# Face_MainBack1V0.net
KiCad netlist of a schematic drawn in Altium Designer
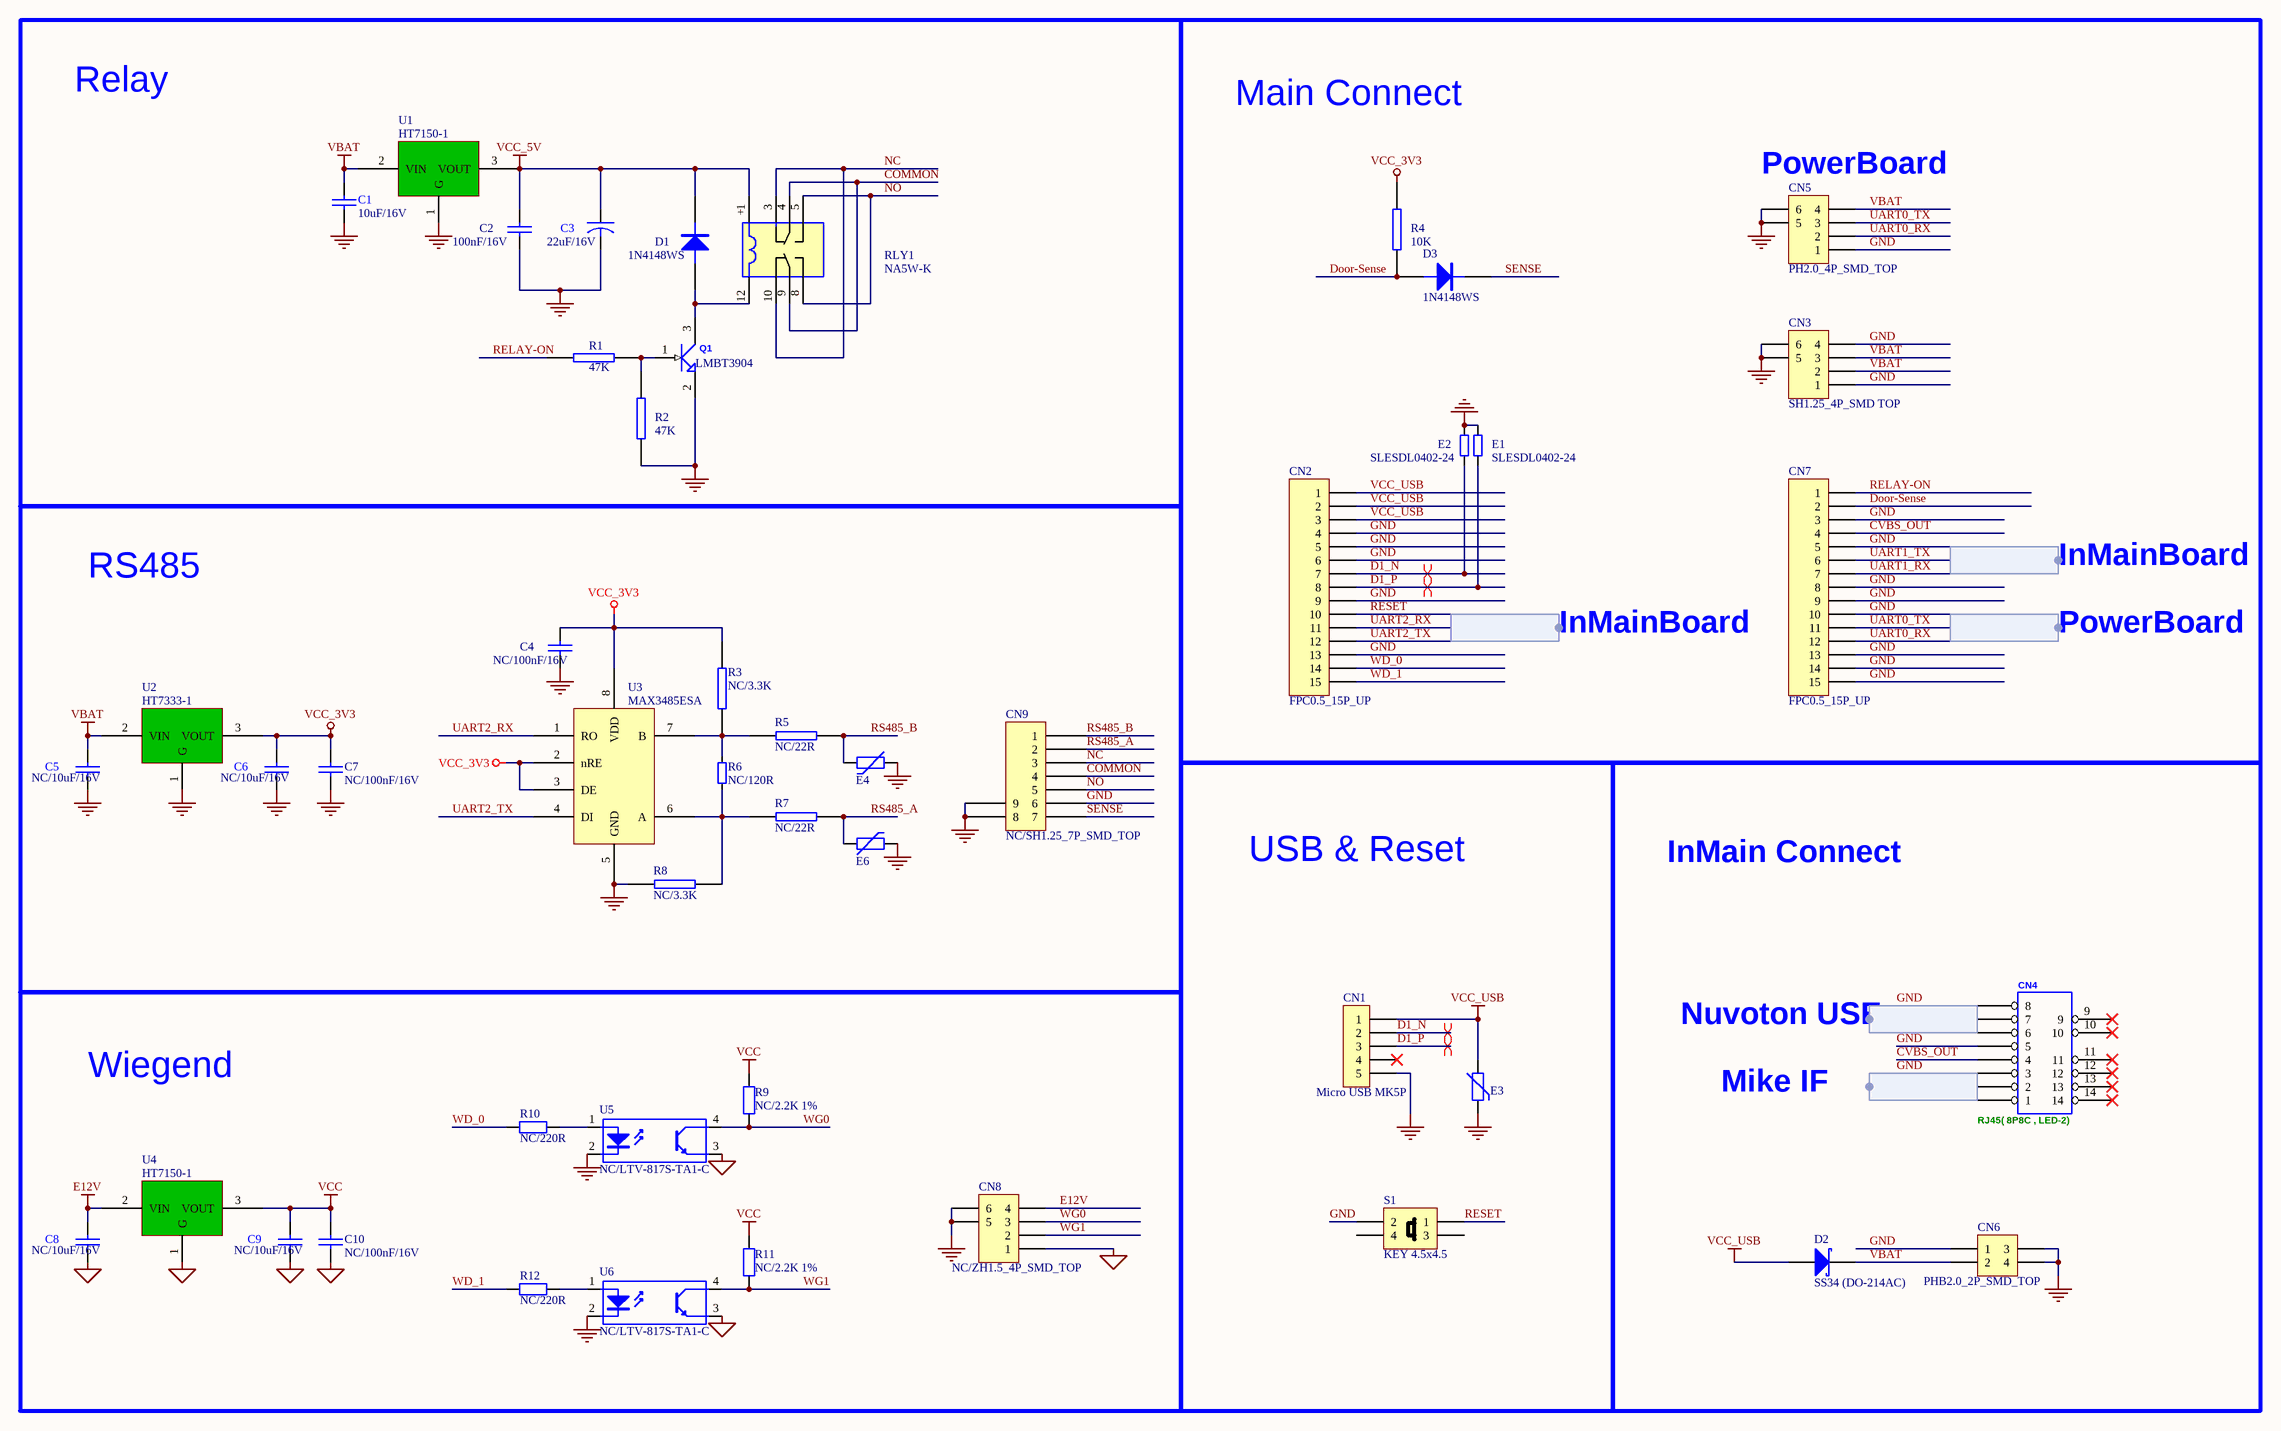
[diagram p0: Face_MainBack1V0.SchDoc]

(export (version "E")
  (design (tool "Eeschema 10.0.6"))
  (components
    (comp (ref "C1")
      (value "10uF/16V")
      (footprint "C0805")
      (description "10uF/16V 10% 0805 X7R ROHS")
      (libsource (lib "*") (part "CAP"))
    )
    (comp (ref "C2")
      (value "100nF/16V")
      (footprint "C0402")
      (description "100nF/16V 10% 0402 X7R ROHS")
      (libsource (lib "*") (part "CAP"))
    )
    (comp (ref "C3")
      (value "22uF/16V")
      (footprint "C0805")
      (description "22uF/16V 20% 0805 X7R ROHS")
      (libsource (lib "*") (part "CAPACITOR"))
    )
    (comp (ref "C4")
      (value "NC/100nF/16V")
      (footprint "C0402")
      (description "100nF/16V 10% 0402 X7R ROHS")
      (libsource (lib "*") (part "CAP"))
    )
    (comp (ref "C5")
      (value "NC/10uF/16V")
      (footprint "C0805")
      (description "10uF/16V 10% 0805 X7R ROHS")
      (libsource (lib "*") (part "CAP"))
    )
    (comp (ref "C6")
      (value "NC/10uF/16V")
      (footprint "C0805")
      (description "10uF/16V 10% 0805 X7R ROHS")
      (libsource (lib "*") (part "CAP"))
    )
    (comp (ref "C7")
      (value "NC/100nF/16V")
      (footprint "C0402")
      (description "100nF/16V 10% 0402 X7R ROHS")
      (libsource (lib "*") (part "CAP"))
    )
    (comp (ref "C8")
      (value "NC/10uF/16V")
      (footprint "C0805")
      (description "10uF/16V 10% 0805 X7R ROHS")
      (libsource (lib "*") (part "CAP"))
    )
    (comp (ref "C9")
      (value "NC/10uF/16V")
      (footprint "C0805")
      (description "10uF/16V 10% 0805 X7R ROHS")
      (libsource (lib "*") (part "CAP"))
    )
    (comp (ref "C10")
      (value "NC/100nF/16V")
      (footprint "C0402")
      (description "100nF/16V 10% 0402 X7R ROHS")
      (libsource (lib "*") (part "CAP"))
    )
    (comp (ref "CN1")
      (value "micro USB")
      (footprint "MICRO_5P_??")
      (description "Micro USB")
      (fields (field (name "ALTIUM_UNNAMED_1") "Micro USB MK5P"))
      (libsource (lib "PCB_Project") (part "CON5"))
    )
    (comp (ref "CN2")
      (value "FPC0.5_15P_UP")
      (footprint "FPC15_0.5_BOTTOM_Drawer")
      (fields (field (name "PUBLISHER") "Altium Limited"))
      (libsource (lib "Miscellaneous Connectors") (part "Header 15"))
    )
    (comp (ref "CN3")
      (value "SH1.25_4P_SMD TOP")
      (footprint "SH1.25_4P_SMD_TOP")
      (fields (field (name "PUBLISHER") "Altium Limited"))
      (libsource (lib "S10_Project") (part "Header 4"))
    )
    (comp (ref "CN4") (value "RJ45( 8P8C , LED-2)") (footprint "RJ45_S") (libsource (lib "*") (part "RJ45")))
    (comp (ref "CN5")
      (value "PH2.0_4P_SMD_TOP")
      (footprint "PH2.0_4P_SMD_TOP")
      (fields (field (name "PUBLISHER") "Altium Limited"))
      (libsource (lib "S10_Project") (part "Header 4"))
    )
    (comp (ref "CN6")
      (value "PHB2.0_2P_SMD_TOP")
      (footprint "PH2.0_2P_SMD_TOP")
      (libsource (lib "FIX Board1V1") (part "Header 2"))
    )
    (comp (ref "CN7")
      (value "FPC0.5_15P_UP")
      (footprint "FPC15_0.5_BOTTOM_Drawer")
      (fields (field (name "PUBLISHER") "Altium Limited"))
      (libsource (lib "Miscellaneous Connectors") (part "Header 15"))
    )
    (comp (ref "CN8")
      (value "NC/ZH1.5_4P_SMD_TOP")
      (footprint "ZH1.5_4P_SMD_TOP")
      (description "ZH1.5_4P_SMD_TOP")
      (fields (field (name "PUBLISHER") "Altium Limited"))
      (libsource (lib "S10_Project") (part "Header 4"))
    )
    (comp (ref "CN9")
      (value "NC/SH1.25_7P_SMD_TOP")
      (footprint "SH1.25_7P_SMD_TOP")
      (description "SH1.25_7P_SMD_TOP")
      (libsource (lib "Schlib1") (part "Component_1"))
    )
    (comp (ref "D1") (value "1N4148WS") (footprint "SOD-323") (libsource (lib "*") (part "DIODE")))
    (comp (ref "D2")
      (value "SS34 (DO-214AC)")
      (footprint "DO-214AC")
      (libsource (lib "LM") (part "SS34 (DO-214AC)"))
    )
    (comp (ref "D3") (value "1N4148WS") (footprint "SOD-323") (libsource (lib "*") (part "DIODE")))
    (comp (ref "E1")
      (value "SLESDL0402-24")
      (footprint "L0402")
      (description "SLESDL0402-24 0402 ROHS")
      (libsource (lib "LM") (part "RES"))
    )
    (comp (ref "E2")
      (value "SLESDL0402-24")
      (footprint "L0402")
      (description "SLESDL0402-24 0402 ROHS")
      (libsource (lib "LM") (part "RES"))
    )
    (comp (ref "E3")
      (value "SFI0402-050E330NP-LF")
      (footprint "R0402")
      (libsource (lib "ZhuhaiSch") (part "VARISTOR"))
    )
    (comp (ref "E4")
      (value "NC/SFI0402-050E330NP-LF")
      (footprint "R0402")
      (description "SFI0402-050E330NP-LF")
      (libsource (lib "ZhuhaiSch") (part "VARISTOR"))
    )
    (comp (ref "E6")
      (value "NC/SFI0402-050E330NP-LF")
      (footprint "R0402")
      (description "SFI0402-050E330NP-LF")
      (libsource (lib "ZhuhaiSch") (part "VARISTOR"))
    )
    (comp (ref "Q1")
      (value "LMBT3904 (SOT-23-3)")
      (footprint "SOT-23-3")
      (fields (field (name "ALTIUM_UNNAMED_1") "LMBT3904"))
      (libsource (lib "*") (part "NPN1"))
    )
    (comp (ref "R1")
      (value "47K")
      (footprint "R0402")
      (description "47K +/-5% 1/16W 0402 ROHS")
      (libsource (lib "*") (part "RES2"))
    )
    (comp (ref "R2")
      (value "47K")
      (footprint "R0402")
      (description "47K +/-5% 1/16W 0402 ROHS")
      (libsource (lib "*") (part "RES2"))
    )
    (comp (ref "R3")
      (value "NC/3.3K")
      (footprint "R0402")
      (description "3.3K +/-5% 1/16W 0402 ROHS")
      (libsource (lib "*") (part "RES2"))
    )
    (comp (ref "R4")
      (value "10K")
      (footprint "R0402")
      (description "10K +/-5% 1/16W 0402 ROHS")
      (libsource (lib "*") (part "RES2"))
    )
    (comp (ref "R5")
      (value "NC/22R")
      (footprint "R0402")
      (description "22R +/-5% 1/16W 0402 ROHS")
      (libsource (lib "*") (part "RES2"))
    )
    (comp (ref "R6")
      (value "NC/120R")
      (footprint "R0402")
      (description "120R +/-5% 1/16W 0402 ROHS")
      (libsource (lib "FL01M1V5") (part "RES2"))
    )
    (comp (ref "R7")
      (value "NC/22R")
      (footprint "R0402")
      (description "22R +/-5% 1/16W 0402 ROHS")
      (libsource (lib "*") (part "RES2"))
    )
    (comp (ref "R8")
      (value "NC/3.3K")
      (footprint "R0402")
      (description "3.3K +/-5% 1/16W 0402 ROHS")
      (libsource (lib "*") (part "RES2"))
    )
    (comp (ref "R9")
      (value "NC/2.2K 1%")
      (footprint "R0402")
      (description "2.2K +/-1% 1/16W 0402 ROHS")
      (fields (field (name "PUBLISHER") "Altium Limited"))
      (libsource (lib "Miscellaneous Devices") (part "Res2"))
    )
    (comp (ref "R10")
      (value "NC/220R")
      (footprint "R0402")
      (description "220R +/-5% 1/16W 0402 ROHS")
      (fields (field (name "PUBLISHER") "Altium Limited"))
      (libsource (lib "") (part "Res2_1"))
    )
    (comp (ref "R11")
      (value "NC/2.2K 1%")
      (footprint "R0402")
      (description "2.2K +/-1% 1/16W 0402 ROHS")
      (fields (field (name "PUBLISHER") "Altium Limited"))
      (libsource (lib "Miscellaneous Devices") (part "Res2"))
    )
    (comp (ref "R12")
      (value "NC/220R")
      (footprint "R0402")
      (description "220R +/-5% 1/16W 0402 ROHS")
      (fields (field (name "PUBLISHER") "Altium Limited"))
      (libsource (lib "") (part "Res2_1"))
    )
    (comp (ref "RLY1")
      (value "FUJITSU NA5W-K     DPDT-BM 5V")
      (footprint "NA12W-K")
      (fields (field (name "ALTIUM_UNNAMED_1") "NA5W-K"))
      (libsource (lib "*") (part "RELAY4"))
    )
    (comp (ref "S1")
      (value "KEY 4.5x4.5")
      (footprint "KEY4.5*4.5-5mm-R")
      (description "KEY6x6x14")
      (fields (field (name "PUBLISHER") "Altium Limited"))
      (libsource (lib "*") (part "Header 2X2H"))
    )
    (comp (ref "U1")
      (value "HT7150-1 (SOT-89)")
      (footprint "SOT-89")
      (description "IC")
      (fields (field (name "ALTIUM_UNNAMED_1") "HT7150-1"))
      (libsource (lib "*") (part "HT7333"))
    )
    (comp (ref "U2")
      (value "NC/HT7333-1 (SOT-89)")
      (footprint "SOT-89")
      (fields (field (name "ALTIUM_UNNAMED_1") "HT7333-1"))
      (libsource (lib "*") (part "HT7333"))
    )
    (comp (ref "U3")
      (value "NC/MAX3485ESA(SOIC-8)")
      (footprint "SOIC8")
      (fields (field (name "ALTIUM_UNNAMED_1") "MAX3485ESA"))
      (libsource (lib "*") (part "MAX485"))
    )
    (comp (ref "U4")
      (value "NC/HT7150-1 (SOT-89)")
      (footprint "SOT-89")
      (fields (field (name "ALTIUM_UNNAMED_1") "HT7150-1"))
      (libsource (lib "*") (part "HT7333"))
    )
    (comp (ref "U5")
      (value "NC/LTV-817S-TA1-C")
      (footprint "LTV-817S-TA1-C")
      (description "LTV-817S-TA1-C")
      (fields (field (name "PUBLISHER") "Altium Limited"))
      (libsource (lib "Miscellaneous Devices") (part "Optoisolator1"))
    )
    (comp (ref "U6")
      (value "NC/LTV-817S-TA1-C")
      (footprint "LTV-817S-TA1-C")
      (description "LTV-817S-TA1-C")
      (fields (field (name "PUBLISHER") "Altium Limited"))
      (libsource (lib "Miscellaneous Devices") (part "Optoisolator1"))
    )
  )
  (nets
    (net (code "1") (name "/COMMON") (class "Default")
      (node (ref "CN9") (pin "4") (pinfunction "4_4") (pintype "passive"))
      (node (ref "RLY1") (pin "4") (pinfunction "4_4") (pintype "passive"))
      (node (ref "RLY1") (pin "9") (pinfunction "9_9") (pintype "passive"))
    )
    (net (code "2") (name "/CVBS_OUT") (class "Default")
      (node (ref "CN4") (pin "4") (pinfunction "4_4") (pintype "passive"))
      (node (ref "CN7") (pin "4") (pinfunction "4_4") (pintype "passive"))
    )
    (net (code "3") (name "/D1_N") (class "Default")
      (node (ref "CN1") (pin "2") (pinfunction "2_2") (pintype "passive"))
      (node (ref "CN2") (pin "7") (pinfunction "7_7") (pintype "passive"))
      (node (ref "E2") (pin "2") (pinfunction "2_2") (pintype "passive"))
    )
    (net (code "4") (name "/D1_P") (class "Default")
      (node (ref "CN1") (pin "3") (pinfunction "3_3") (pintype "passive"))
      (node (ref "CN2") (pin "8") (pinfunction "8_8") (pintype "passive"))
      (node (ref "E1") (pin "1") (pinfunction "1_1") (pintype "passive"))
    )
    (net (code "5") (name "/Door-Sense") (class "Default")
      (node (ref "CN7") (pin "2") (pinfunction "2_2") (pintype "passive"))
      (node (ref "D3") (pin "1") (pinfunction "A_1") (pintype "passive"))
      (node (ref "R4") (pin "2") (pinfunction "2_2") (pintype "passive"))
    )
    (net (code "6") (name "/NC") (class "Default")
      (node (ref "CN9") (pin "3") (pinfunction "3_3") (pintype "passive"))
      (node (ref "RLY1") (pin "10") (pinfunction "10_10") (pintype "passive"))
      (node (ref "RLY1") (pin "3") (pinfunction "3_3") (pintype "passive"))
    )
    (net (code "7") (name "/NO") (class "Default")
      (node (ref "CN9") (pin "5") (pinfunction "5_5") (pintype "passive"))
      (node (ref "RLY1") (pin "5") (pinfunction "5_5") (pintype "passive"))
      (node (ref "RLY1") (pin "8") (pinfunction "8_8") (pintype "passive"))
    )
    (net (code "8") (name "/RELAY-ON") (class "Default")
      (node (ref "CN7") (pin "1") (pinfunction "1_1") (pintype "passive"))
      (node (ref "R1") (pin "2") (pinfunction "2_2") (pintype "passive"))
    )
    (net (code "9") (name "/RESET") (class "Default")
      (node (ref "CN2") (pin "10") (pinfunction "10_10") (pintype "passive"))
      (node (ref "S1") (pin "1") (pinfunction "1_1") (pintype "passive"))
    )
    (net (code "10") (name "/RS485_A") (class "Default")
      (node (ref "CN9") (pin "2") (pinfunction "2_2") (pintype "passive"))
      (node (ref "E6") (pin "1") (pinfunction "1_1") (pintype "passive"))
      (node (ref "R7") (pin "2") (pinfunction "2_2") (pintype "passive"))
    )
    (net (code "11") (name "/RS485_B") (class "Default")
      (node (ref "CN9") (pin "1") (pinfunction "1_1") (pintype "passive"))
      (node (ref "E4") (pin "2") (pinfunction "2_2") (pintype "passive"))
      (node (ref "R5") (pin "2") (pinfunction "2_2") (pintype "passive"))
    )
    (net (code "12") (name "/SENSE") (class "Default")
      (node (ref "CN9") (pin "7") (pinfunction "7_7") (pintype "passive"))
      (node (ref "D3") (pin "2") (pinfunction "K_2") (pintype "passive"))
    )
    (net (code "13") (name "/UART0_RX") (class "Default")
      (node (ref "CN5") (pin "2") (pinfunction "2_2") (pintype "passive"))
      (node (ref "CN7") (pin "12") (pinfunction "12_12") (pintype "passive"))
    )
    (net (code "14") (name "/UART0_TX") (class "Default")
      (node (ref "CN5") (pin "3") (pinfunction "3_3") (pintype "passive"))
      (node (ref "CN7") (pin "11") (pinfunction "11_11") (pintype "passive"))
    )
    (net (code "15") (name "/UART1_RX") (class "Default")
      (node (ref "CN4") (pin "1") (pinfunction "1_1") (pintype "passive"))
      (node (ref "CN7") (pin "7") (pinfunction "7_7") (pintype "passive"))
    )
    (net (code "16") (name "/UART1_TX") (class "Default")
      (node (ref "CN4") (pin "2") (pinfunction "2_2") (pintype "passive"))
      (node (ref "CN7") (pin "6") (pinfunction "6_6") (pintype "passive"))
    )
    (net (code "17") (name "/UART2_RX") (class "Default")
      (node (ref "CN2") (pin "11") (pinfunction "11_11") (pintype "passive"))
      (node (ref "CN4") (pin "7") (pinfunction "7_7") (pintype "passive"))
      (node (ref "U3") (pin "1") (pinfunction "RO_1") (pintype "passive"))
    )
    (net (code "18") (name "/UART2_TX") (class "Default")
      (node (ref "CN2") (pin "12") (pinfunction "12_12") (pintype "passive"))
      (node (ref "CN4") (pin "6") (pinfunction "6_6") (pintype "passive"))
      (node (ref "U3") (pin "4") (pinfunction "DI_4") (pintype "passive"))
    )
    (net (code "19") (name "/WD_0") (class "Default")
      (node (ref "CN2") (pin "14") (pinfunction "14_14") (pintype "passive"))
      (node (ref "R10") (pin "1") (pinfunction "1_1") (pintype "passive"))
    )
    (net (code "20") (name "/WD_1") (class "Default")
      (node (ref "CN2") (pin "15") (pinfunction "15_15") (pintype "passive"))
      (node (ref "R12") (pin "1") (pinfunction "1_1") (pintype "passive"))
    )
    (net (code "21") (name "/WG0") (class "Default")
      (node (ref "CN8") (pin "3") (pinfunction "3_3") (pintype "passive"))
      (node (ref "R9") (pin "1") (pinfunction "1_1") (pintype "passive"))
      (node (ref "U5") (pin "4") (pinfunction "C_4") (pintype "passive"))
    )
    (net (code "22") (name "/WG1") (class "Default")
      (node (ref "CN8") (pin "2") (pinfunction "2_2") (pintype "passive"))
      (node (ref "R11") (pin "1") (pinfunction "1_1") (pintype "passive"))
      (node (ref "U6") (pin "4") (pinfunction "C_4") (pintype "passive"))
    )
    (net (code "23") (name "E12V") (class "Default")
      (node (ref "C8") (pin "2") (pinfunction "2_2") (pintype "passive"))
      (node (ref "CN8") (pin "4") (pinfunction "4_4") (pintype "passive"))
      (node (ref "U4") (pin "2") (pinfunction "VIN_2") (pintype "passive"))
    )
    (net (code "24") (name "FGND") (class "Default")
      (node (ref "C10") (pin "1") (pinfunction "1_1") (pintype "passive"))
      (node (ref "C8") (pin "1") (pinfunction "1_1") (pintype "passive"))
      (node (ref "C9") (pin "1") (pinfunction "1_1") (pintype "passive"))
      (node (ref "CN8") (pin "1") (pinfunction "1_1") (pintype "passive"))
      (node (ref "U4") (pin "1") (pinfunction "G_1") (pintype "passive"))
      (node (ref "U5") (pin "3") (pinfunction "E_3") (pintype "passive"))
      (node (ref "U6") (pin "3") (pinfunction "E_3") (pintype "passive"))
    )
    (net (code "25") (name "GND") (class "Default")
      (node (ref "C1") (pin "2") (pinfunction "2_2") (pintype "passive"))
      (node (ref "C2") (pin "1") (pinfunction "1_1") (pintype "passive"))
      (node (ref "C3") (pin "2") (pinfunction "2_2") (pintype "passive"))
      (node (ref "C4") (pin "1") (pinfunction "1_1") (pintype "passive"))
      (node (ref "C5") (pin "1") (pinfunction "1_1") (pintype "passive"))
      (node (ref "C6") (pin "1") (pinfunction "1_1") (pintype "passive"))
      (node (ref "C7") (pin "1") (pinfunction "1_1") (pintype "passive"))
      (node (ref "CN1") (pin "5") (pinfunction "5_5") (pintype "passive"))
      (node (ref "CN2") (pin "13") (pinfunction "13_13") (pintype "passive"))
      (node (ref "CN2") (pin "4") (pinfunction "4_4") (pintype "passive"))
      (node (ref "CN2") (pin "5") (pinfunction "5_5") (pintype "passive"))
      (node (ref "CN2") (pin "6") (pinfunction "6_6") (pintype "passive"))
      (node (ref "CN2") (pin "9") (pinfunction "9_9") (pintype "passive"))
      (node (ref "CN3") (pin "1") (pinfunction "1_1") (pintype "passive"))
      (node (ref "CN3") (pin "4") (pinfunction "4_4") (pintype "passive"))
      (node (ref "CN3") (pin "5") (pinfunction "5_5") (pintype "passive"))
      (node (ref "CN3") (pin "6") (pinfunction "6_6") (pintype "passive"))
      (node (ref "CN4") (pin "3") (pinfunction "3_3") (pintype "passive"))
      (node (ref "CN4") (pin "5") (pinfunction "5_5") (pintype "passive"))
      (node (ref "CN4") (pin "8") (pinfunction "8_8") (pintype "passive"))
      (node (ref "CN5") (pin "1") (pinfunction "1_1") (pintype "passive"))
      (node (ref "CN5") (pin "5") (pinfunction "5_5") (pintype "passive"))
      (node (ref "CN5") (pin "6") (pinfunction "6_6") (pintype "passive"))
      (node (ref "CN6") (pin "1") (pinfunction "1_1") (pintype "passive"))
      (node (ref "CN6") (pin "3") (pinfunction "3_3") (pintype "passive"))
      (node (ref "CN6") (pin "4") (pinfunction "4_4") (pintype "passive"))
      (node (ref "CN7") (pin "10") (pinfunction "10_10") (pintype "passive"))
      (node (ref "CN7") (pin "13") (pinfunction "13_13") (pintype "passive"))
      (node (ref "CN7") (pin "14") (pinfunction "14_14") (pintype "passive"))
      (node (ref "CN7") (pin "15") (pinfunction "15_15") (pintype "passive"))
      (node (ref "CN7") (pin "3") (pinfunction "3_3") (pintype "passive"))
      (node (ref "CN7") (pin "5") (pinfunction "5_5") (pintype "passive"))
      (node (ref "CN7") (pin "8") (pinfunction "8_8") (pintype "passive"))
      (node (ref "CN7") (pin "9") (pinfunction "9_9") (pintype "passive"))
      (node (ref "CN8") (pin "5") (pinfunction "5_5") (pintype "passive"))
      (node (ref "CN8") (pin "6") (pinfunction "6_6") (pintype "passive"))
      (node (ref "CN9") (pin "6") (pinfunction "6_6") (pintype "passive"))
      (node (ref "CN9") (pin "8") (pinfunction "8_8") (pintype "passive"))
      (node (ref "CN9") (pin "9") (pinfunction "9_9") (pintype "passive"))
      (node (ref "E1") (pin "2") (pinfunction "2_2") (pintype "passive"))
      (node (ref "E2") (pin "1") (pinfunction "1_1") (pintype "passive"))
      (node (ref "E3") (pin "2") (pinfunction "2_2") (pintype "passive"))
      (node (ref "E4") (pin "1") (pinfunction "1_1") (pintype "passive"))
      (node (ref "E6") (pin "2") (pinfunction "2_2") (pintype "passive"))
      (node (ref "Q1") (pin "2") (pinfunction "E_2") (pintype "passive"))
      (node (ref "R2") (pin "2") (pinfunction "2_2") (pintype "passive"))
      (node (ref "R8") (pin "2") (pinfunction "2_2") (pintype "passive"))
      (node (ref "S1") (pin "2") (pinfunction "2_2") (pintype "passive"))
      (node (ref "U1") (pin "1") (pinfunction "G_1") (pintype "passive"))
      (node (ref "U2") (pin "1") (pinfunction "G_1") (pintype "passive"))
      (node (ref "U3") (pin "5") (pinfunction "GND_5") (pintype "passive"))
      (node (ref "U5") (pin "2") (pinfunction "K_2") (pintype "passive"))
      (node (ref "U6") (pin "2") (pinfunction "K_2") (pintype "passive"))
    )
    (net (code "26") (name "Net-(D1-A)") (class "Default")
      (node (ref "D1") (pin "1") (pinfunction "A_1") (pintype "passive"))
      (node (ref "Q1") (pin "3") (pinfunction "C_3") (pintype "passive"))
      (node (ref "RLY1") (pin "12") (pinfunction "12_12") (pintype "passive"))
    )
    (net (code "27") (name "Net-(Q1-B)") (class "Default")
      (node (ref "Q1") (pin "1") (pinfunction "B_1") (pintype "input"))
      (node (ref "R1") (pin "1") (pinfunction "1_1") (pintype "passive"))
      (node (ref "R2") (pin "1") (pinfunction "1_1") (pintype "passive"))
    )
    (net (code "28") (name "Net-(U3-A)") (class "Default")
      (node (ref "R6") (pin "2") (pinfunction "2_2") (pintype "passive"))
      (node (ref "R7") (pin "1") (pinfunction "1_1") (pintype "passive"))
      (node (ref "R8") (pin "1") (pinfunction "1_1") (pintype "passive"))
      (node (ref "U3") (pin "6") (pinfunction "A_6") (pintype "passive"))
    )
    (net (code "29") (name "Net-(U3-B)") (class "Default")
      (node (ref "R3") (pin "2") (pinfunction "2_2") (pintype "passive"))
      (node (ref "R5") (pin "1") (pinfunction "1_1") (pintype "passive"))
      (node (ref "R6") (pin "1") (pinfunction "1_1") (pintype "passive"))
      (node (ref "U3") (pin "7") (pinfunction "B_7") (pintype "passive"))
    )
    (net (code "30") (name "Net-(U5-A)") (class "Default")
      (node (ref "R10") (pin "2") (pinfunction "2_2") (pintype "passive"))
      (node (ref "U5") (pin "1") (pinfunction "A_1") (pintype "passive"))
    )
    (net (code "31") (name "Net-(U6-A)") (class "Default")
      (node (ref "R12") (pin "2") (pinfunction "2_2") (pintype "passive"))
      (node (ref "U6") (pin "1") (pinfunction "A_1") (pintype "passive"))
    )
    (net (code "32") (name "VBAT") (class "Default")
      (node (ref "C1") (pin "1") (pinfunction "1_1") (pintype "passive"))
      (node (ref "C5") (pin "2") (pinfunction "2_2") (pintype "passive"))
      (node (ref "CN3") (pin "2") (pinfunction "2_2") (pintype "passive"))
      (node (ref "CN3") (pin "3") (pinfunction "3_3") (pintype "passive"))
      (node (ref "CN5") (pin "4") (pinfunction "4_4") (pintype "passive"))
      (node (ref "CN6") (pin "2") (pinfunction "2_2") (pintype "passive"))
      (node (ref "D2") (pin "2") (pinfunction "K_2") (pintype "passive"))
      (node (ref "U1") (pin "2") (pinfunction "VIN_2") (pintype "passive"))
      (node (ref "U2") (pin "2") (pinfunction "VIN_2") (pintype "passive"))
    )
    (net (code "33") (name "VCC") (class "Default")
      (node (ref "C10") (pin "2") (pinfunction "2_2") (pintype "passive"))
      (node (ref "C9") (pin "2") (pinfunction "2_2") (pintype "passive"))
      (node (ref "R11") (pin "2") (pinfunction "2_2") (pintype "passive"))
      (node (ref "R9") (pin "2") (pinfunction "2_2") (pintype "passive"))
      (node (ref "U4") (pin "3") (pinfunction "VOUT_3") (pintype "passive"))
    )
    (net (code "34") (name "VCC_3V3") (class "Default")
      (node (ref "C4") (pin "2") (pinfunction "2_2") (pintype "passive"))
      (node (ref "C6") (pin "2") (pinfunction "2_2") (pintype "passive"))
      (node (ref "C7") (pin "2") (pinfunction "2_2") (pintype "passive"))
      (node (ref "R3") (pin "1") (pinfunction "1_1") (pintype "passive"))
      (node (ref "R4") (pin "1") (pinfunction "1_1") (pintype "passive"))
      (node (ref "U2") (pin "3") (pinfunction "VOUT_3") (pintype "passive"))
      (node (ref "U3") (pin "2") (pinfunction "nRE_2") (pintype "passive"))
      (node (ref "U3") (pin "3") (pinfunction "DE_3") (pintype "passive"))
      (node (ref "U3") (pin "8") (pinfunction "VDD_8") (pintype "passive"))
    )
    (net (code "35") (name "VCC_5V") (class "Default")
      (node (ref "C2") (pin "2") (pinfunction "2_2") (pintype "passive"))
      (node (ref "C3") (pin "1") (pinfunction "1_1") (pintype "passive"))
      (node (ref "D1") (pin "2") (pinfunction "K_2") (pintype "passive"))
      (node (ref "RLY1") (pin "1") (pinfunction "1_1") (pintype "passive"))
      (node (ref "U1") (pin "3") (pinfunction "VOUT_3") (pintype "passive"))
    )
    (net (code "36") (name "VCC_USB") (class "Default")
      (node (ref "CN1") (pin "1") (pinfunction "1_1") (pintype "passive"))
      (node (ref "CN2") (pin "1") (pinfunction "1_1") (pintype "passive"))
      (node (ref "CN2") (pin "2") (pinfunction "2_2") (pintype "passive"))
      (node (ref "CN2") (pin "3") (pinfunction "3_3") (pintype "passive"))
      (node (ref "D2") (pin "1") (pinfunction "A_1") (pintype "passive"))
      (node (ref "E3") (pin "1") (pinfunction "1_1") (pintype "passive"))
    )
    (net (code "37") (name "unconnected-(CN1-Pad4)") (class "Default")
      (node (ref "CN1") (pin "4") (pinfunction "4_4") (pintype "passive+no_connect"))
    )
    (net (code "38") (name "unconnected-(CN4-Pad9)") (class "Default")
      (node (ref "CN4") (pin "9") (pinfunction "9_9") (pintype "passive+no_connect"))
    )
    (net (code "39") (name "unconnected-(CN4-Pad10)") (class "Default")
      (node (ref "CN4") (pin "10") (pinfunction "10_10") (pintype "passive+no_connect"))
    )
    (net (code "40") (name "unconnected-(CN4-Pad11)") (class "Default")
      (node (ref "CN4") (pin "11") (pinfunction "11_11") (pintype "passive+no_connect"))
    )
    (net (code "41") (name "unconnected-(CN4-Pad12)") (class "Default")
      (node (ref "CN4") (pin "12") (pinfunction "12_12") (pintype "passive+no_connect"))
    )
    (net (code "42") (name "unconnected-(CN4-Pad13)") (class "Default")
      (node (ref "CN4") (pin "13") (pinfunction "13_13") (pintype "passive+no_connect"))
    )
    (net (code "43") (name "unconnected-(CN4-Pad14)") (class "Default")
      (node (ref "CN4") (pin "14") (pinfunction "14_14") (pintype "passive+no_connect"))
    )
    (net (code "44") (name "unconnected-(S1-Pad3)") (class "Default")
      (node (ref "S1") (pin "3") (pinfunction "3_3") (pintype "passive"))
    )
    (net (code "45") (name "unconnected-(S1-Pad4)") (class "Default")
      (node (ref "S1") (pin "4") (pinfunction "4_4") (pintype "passive"))
    )
  )
)
